# logi-cam-mt9v.net
KiCad netlist of a schematic drawn in Altium Designer
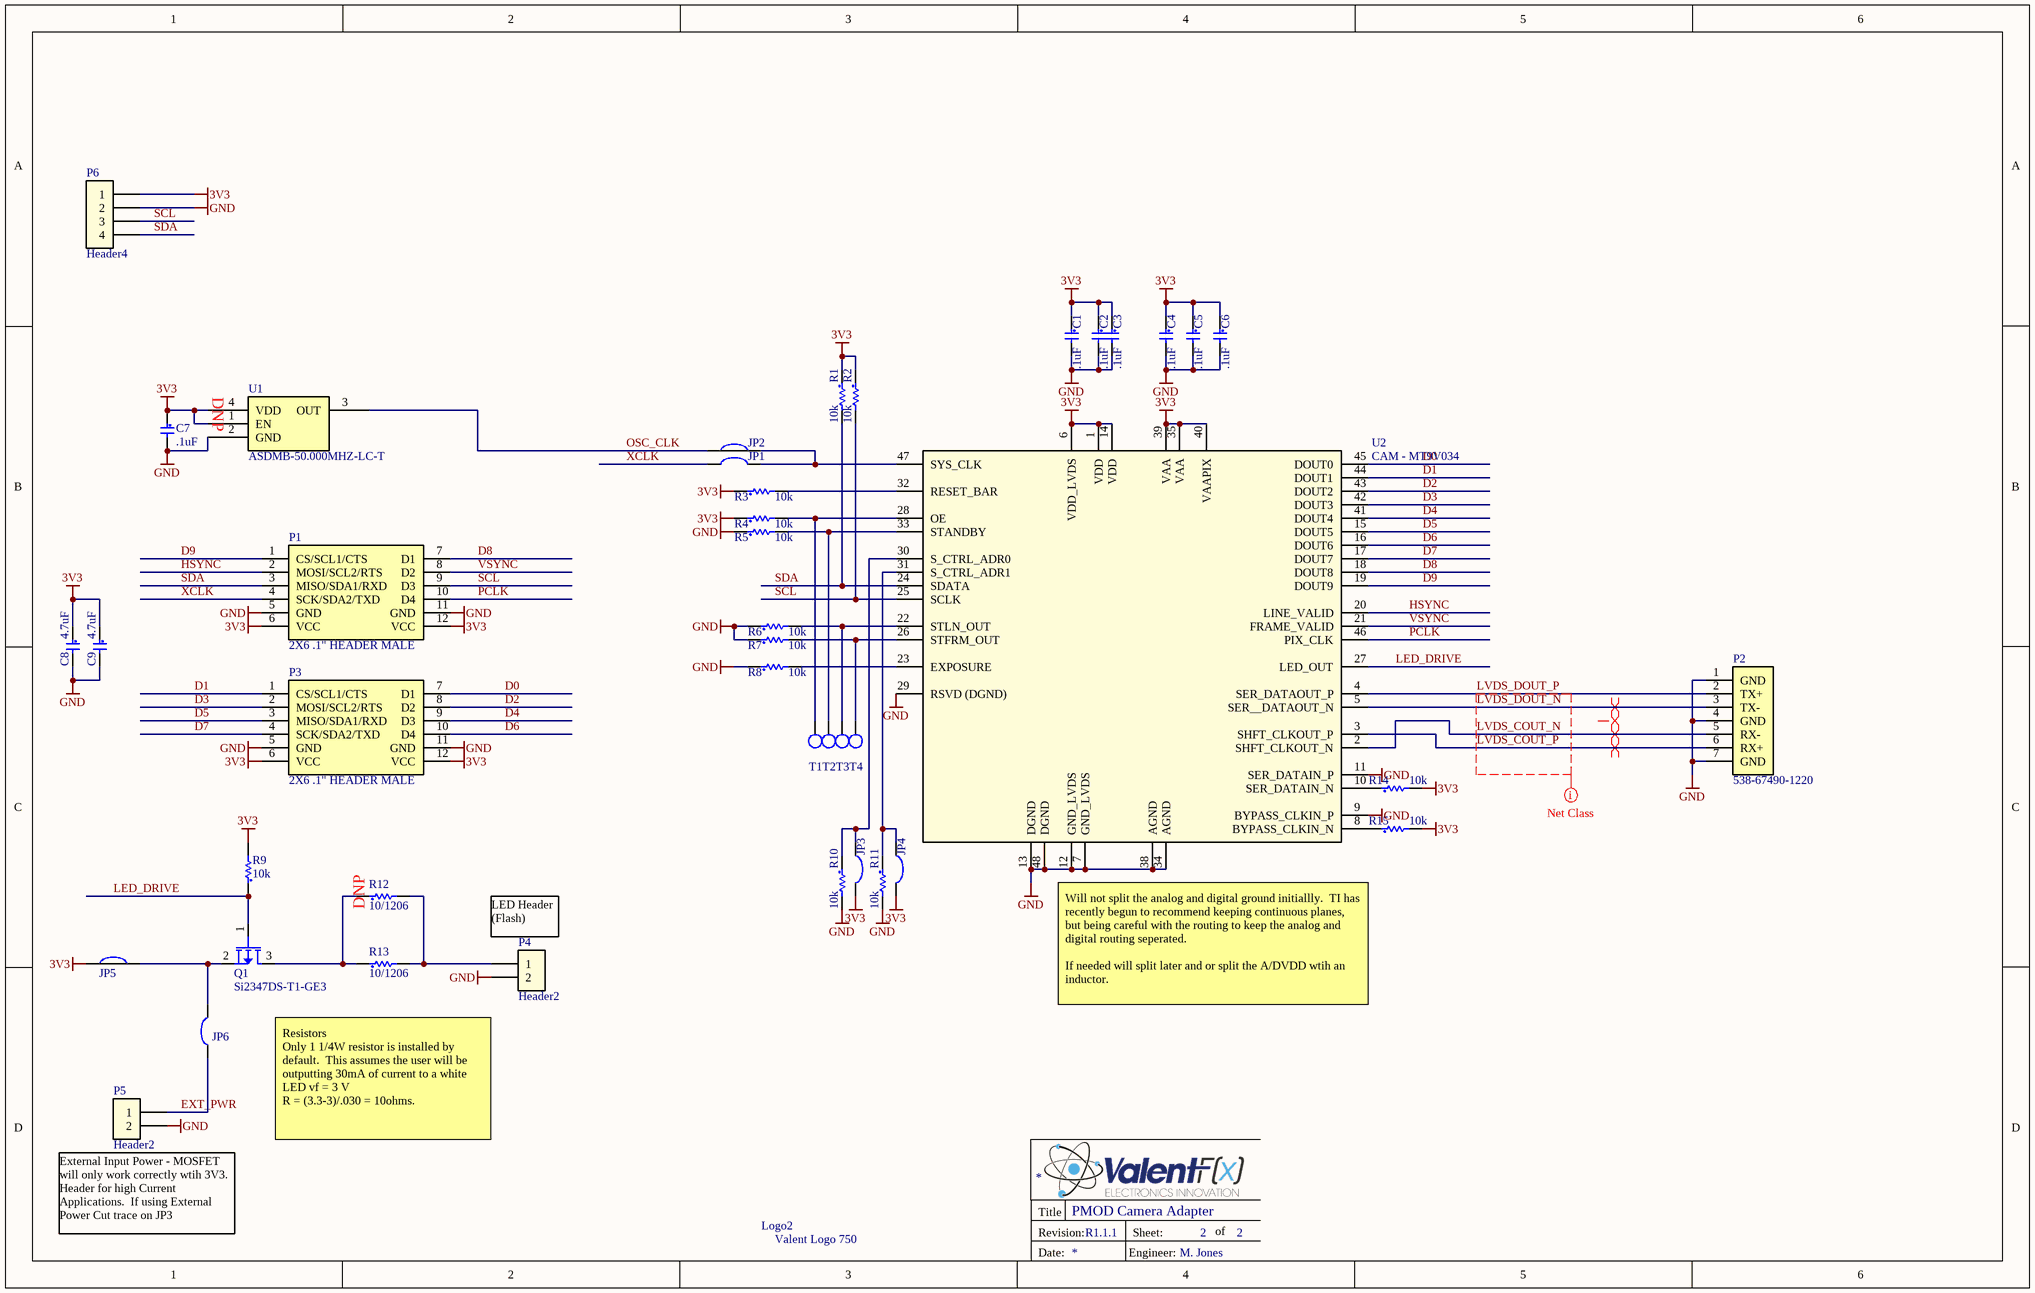
[diagram p0: logi-cam-mt9v.SchDoc]

(export (version "E")
  (design (tool "Eeschema 10.0.6"))
  (components
    (comp (ref "C1")
      (value ".1uF")
      (footprint "mRCL:C0603")
      (description ".10uF X7R 20% (MLCC) - SMD/SMT 0603 25volts")
      (fields (field (name "MANUFACTURER") "TDK") (field (name "MANUFACTURER PART NUMBER") "C1608X7R1E104MT"))
      (libsource (lib "mCapacitors") (part "C0603 - C1608X7R1E104MT"))
    )
    (comp (ref "C2")
      (value ".1uF")
      (footprint "mRCL:C0603")
      (description ".10uF X7R 20% (MLCC) - SMD/SMT 0603 25volts")
      (fields (field (name "MANUFACTURER") "TDK") (field (name "MANUFACTURER PART NUMBER") "C1608X7R1E104MT"))
      (libsource (lib "mCapacitors") (part "C0603 - C1608X7R1E104MT"))
    )
    (comp (ref "C3")
      (value ".1uF")
      (footprint "mRCL:C0603")
      (description ".10uF X7R 20% (MLCC) - SMD/SMT 0603 25volts")
      (fields (field (name "MANUFACTURER") "TDK") (field (name "MANUFACTURER PART NUMBER") "C1608X7R1E104MT"))
      (libsource (lib "mCapacitors") (part "C0603 - C1608X7R1E104MT"))
    )
    (comp (ref "C4")
      (value ".1uF")
      (footprint "mRCL:C0603")
      (description ".10uF X7R 20% (MLCC) - SMD/SMT 0603 25volts")
      (fields (field (name "MANUFACTURER") "TDK") (field (name "MANUFACTURER PART NUMBER") "C1608X7R1E104MT"))
      (libsource (lib "mCapacitors") (part "C0603 - C1608X7R1E104MT"))
    )
    (comp (ref "C5")
      (value ".1uF")
      (footprint "mRCL:C0603")
      (description ".10uF X7R 20% (MLCC) - SMD/SMT 0603 25volts")
      (fields (field (name "MANUFACTURER") "TDK") (field (name "MANUFACTURER PART NUMBER") "C1608X7R1E104MT"))
      (libsource (lib "mCapacitors") (part "C0603 - C1608X7R1E104MT"))
    )
    (comp (ref "C6")
      (value ".1uF")
      (footprint "mRCL:C0603")
      (description ".10uF X7R 20% (MLCC) - SMD/SMT 0603 25volts")
      (fields (field (name "MANUFACTURER") "TDK") (field (name "MANUFACTURER PART NUMBER") "C1608X7R1E104MT"))
      (libsource (lib "mCapacitors") (part "C0603 - C1608X7R1E104MT"))
    )
    (comp (ref "C7")
      (value ".1uF")
      (footprint "mRCL:C0603")
      (description ".10uF X7R 20% (MLCC) - SMD/SMT 0603 25volts")
      (fields (field (name "MANUFACTURER") "TDK") (field (name "MANUFACTURER PART NUMBER") "C1608X7R1E104MT"))
      (libsource (lib "mCapacitors") (part "C0603 - C1608X7R1E104MT"))
    )
    (comp (ref "C8")
      (value "4.7uF")
      (footprint "C0603 - Marked")
      (description "4.7uF 6.3volts X5R 10% (MLCC) - SMD/SMT 0603")
      (fields
        (field (name "MANUFACTURER") "Murata Electronics North America")
        (field (name "MANUFACTURER PART NUMBER") "GRM188R60J475KE19D")
      )
      (libsource (lib "mCapacitors") (part "C0603 - GRM188R60J475KE19D"))
    )
    (comp (ref "C9")
      (value "4.7uF")
      (footprint "C0603 - Marked")
      (description "4.7uF 6.3volts X5R 10% (MLCC) - SMD/SMT 0603")
      (fields
        (field (name "MANUFACTURER") "Murata Electronics North America")
        (field (name "MANUFACTURER PART NUMBER") "GRM188R60J475KE19D")
      )
      (libsource (lib "mCapacitors") (part "C0603 - GRM188R60J475KE19D"))
    )
    (comp (ref "JP1")
      (value "Solder Jumper")
      (footprint "SOLDER_JUMPER")
      (description "Solder/Configuration Jumper")
      (fields (field (name "MANUFACTURER") "n/a"))
      (libsource (lib "") (part "Solder Jumper_1"))
    )
    (comp (ref "JP2")
      (value "Solder Jumper-NC")
      (footprint "SOLDER_JUMPER-NC")
      (description "Solder/Configuration Jumper")
      (fields (field (name "MANUFACTURER") "n/a"))
      (libsource (lib "mConnector") (part "Solder Jumper-NC"))
    )
    (comp (ref "JP3")
      (value "Solder Jumper")
      (footprint "SOLDER_JUMPER")
      (description "Solder/Configuration Jumper")
      (fields (field (name "MANUFACTURER") "n/a"))
      (libsource (lib "mConnector") (part "Solder Jumper"))
    )
    (comp (ref "JP4")
      (value "Solder Jumper")
      (footprint "SOLDER_JUMPER")
      (description "Solder/Configuration Jumper")
      (fields (field (name "MANUFACTURER") "n/a"))
      (libsource (lib "mConnector") (part "Solder Jumper"))
    )
    (comp (ref "JP5")
      (value "Solder Jumper-NC")
      (footprint "SOLDER_JUMPER-NC")
      (description "Solder/Configuration Jumper")
      (fields (field (name "MANUFACTURER") "n/a"))
      (libsource (lib "mConnector") (part "Solder Jumper-NC"))
    )
    (comp (ref "JP6")
      (value "Solder Jumper")
      (footprint "SOLDER_JUMPER")
      (description "Solder/Configuration Jumper")
      (fields (field (name "MANUFACTURER") "n/a"))
      (libsource (lib "mConnector") (part "Solder Jumper"))
    )
    (comp (ref "Logo2")
      (value "Valent Logo 750")
      (footprint "VALENTFX_750-SolderMask-BOT")
      (libsource (lib "mLogos") (part "Valent Logo 750"))
    )
    (comp (ref "P1")
      (value "2X6 .1\" HEADER MALE")
      (footprint "PMOD HEADER - Male Vertical")
      (description "CONN HEADER .100\" DUAL STR 12 POS")
      (fields
        (field (name "MANUFACTURER") "Sullins Connector Solutions")
        (field (name "MANUFACTURER PART NUMBER") "PRPC006DAAN-RC")
      )
      (libsource (lib "mConnector") (part "P-MOD - PRPC006DAAN-RC"))
    )
    (comp (ref "P2")
      (value "SATA - 67490-1220")
      (footprint "SATA - 67490-3220")
      (description "SATA Data - 67490-1220")
      (fields
        (field (name "MANUFACTURER") "Molex")
        (field (name "MANUFACTURER PART NUMBER") "67490-1220")
        (field (name "SUPPLIER PART NUMBER 1") "538-67490-1220")
      )
      (libsource (lib "mConnector") (part "SATA - 67490-1220"))
    )
    (comp (ref "P3")
      (value "2X6 .1\" HEADER MALE")
      (footprint "PMOD HEADER - Male Vertical")
      (description "CONN HEADER .100\" DUAL STR 12 POS")
      (fields
        (field (name "MANUFACTURER") "Sullins Connector Solutions")
        (field (name "MANUFACTURER PART NUMBER") "PRPC006DAAN-RC")
      )
      (libsource (lib "mConnector") (part "P-MOD - PRPC006DAAN-RC"))
    )
    (comp (ref "P4")
      (value "Header2")
      (footprint "HEADER_2_40_100 THRU SIP")
      (description "Header 2 pin")
      (libsource (lib "mConnector") (part "Header2"))
    )
    (comp (ref "P5")
      (value "Header2")
      (footprint "HEADER_2_40_100 THRU SIP")
      (description "Header 2 pin")
      (libsource (lib "") (part "Header2_1"))
    )
    (comp (ref "P6")
      (value "Header4")
      (footprint "HEADER_4_40_100 THRU SIP - duplicate")
      (description "Header 4 pin")
      (libsource (lib "mConnector") (part "Header4"))
    )
    (comp (ref "Q1")
      (value "Si2347DS-T1-GE3")
      (footprint "sot-23")
      (description "MOSFET -30V .042Ohm@10V 5A P-Ch G-III")
      (fields
        (field (name "MANUFACTURER") "Vishay Semiconductors")
        (field (name "ACCEPT COMPATIBLE REPLACEMENT PART") "Yes")
      )
      (libsource (lib "mTransistor") (part "PMOS - Si2347DS-T1-GE3"))
    )
    (comp (ref "R1")
      (value "10k")
      (footprint "mRCL:R0603")
      (description "10k Thick Film Resistors - SMD 1/10watt 10Kohms 1%")
      (fields
        (field (name "MANUFACTURER") "Vishay Dale")
        (field (name "MANUFACTURER PART NUMBER") "CRCW060310K0FKEA")
      )
      (libsource (lib "mResistors") (part "R0603 - CRCW060310K0FKEA"))
    )
    (comp (ref "R2")
      (value "10k")
      (footprint "mRCL:R0603")
      (description "10k Thick Film Resistors - SMD 1/10watt 10Kohms 1%")
      (fields
        (field (name "MANUFACTURER") "Vishay Dale")
        (field (name "MANUFACTURER PART NUMBER") "CRCW060310K0FKEA")
      )
      (libsource (lib "mResistors") (part "R0603 - CRCW060310K0FKEA"))
    )
    (comp (ref "R3")
      (value "10k")
      (footprint "mRCL:R0603")
      (description "10k Thick Film Resistors - SMD 1/10watt 10Kohms 1%")
      (fields
        (field (name "MANUFACTURER") "Vishay Dale")
        (field (name "MANUFACTURER PART NUMBER") "CRCW060310K0FKEA")
      )
      (libsource (lib "mResistors") (part "R0603 - CRCW060310K0FKEA"))
    )
    (comp (ref "R4")
      (value "10k")
      (footprint "mRCL:R0603")
      (description "10k Thick Film Resistors - SMD 1/10watt 10Kohms 1%")
      (fields
        (field (name "MANUFACTURER") "Vishay Dale")
        (field (name "MANUFACTURER PART NUMBER") "CRCW060310K0FKEA")
      )
      (libsource (lib "mResistors") (part "R0603 - CRCW060310K0FKEA"))
    )
    (comp (ref "R5")
      (value "10k")
      (footprint "mRCL:R0603")
      (description "10k Thick Film Resistors - SMD 1/10watt 10Kohms 1%")
      (fields
        (field (name "MANUFACTURER") "Vishay Dale")
        (field (name "MANUFACTURER PART NUMBER") "CRCW060310K0FKEA")
      )
      (libsource (lib "mResistors") (part "R0603 - CRCW060310K0FKEA"))
    )
    (comp (ref "R6")
      (value "10k")
      (footprint "mRCL:R0603")
      (description "10k Thick Film Resistors - SMD 1/10watt 10Kohms 1%")
      (fields
        (field (name "MANUFACTURER") "Vishay Dale")
        (field (name "MANUFACTURER PART NUMBER") "CRCW060310K0FKEA")
      )
      (libsource (lib "mResistors") (part "R0603 - CRCW060310K0FKEA"))
    )
    (comp (ref "R7")
      (value "10k")
      (footprint "mRCL:R0603")
      (description "10k Thick Film Resistors - SMD 1/10watt 10Kohms 1%")
      (fields
        (field (name "MANUFACTURER") "Vishay Dale")
        (field (name "MANUFACTURER PART NUMBER") "CRCW060310K0FKEA")
      )
      (libsource (lib "mResistors") (part "R0603 - CRCW060310K0FKEA"))
    )
    (comp (ref "R8")
      (value "10k")
      (footprint "mRCL:R0603")
      (description "10k Thick Film Resistors - SMD 1/10watt 10Kohms 1%")
      (fields
        (field (name "MANUFACTURER") "Vishay Dale")
        (field (name "MANUFACTURER PART NUMBER") "CRCW060310K0FKEA")
      )
      (libsource (lib "mResistors") (part "R0603 - CRCW060310K0FKEA"))
    )
    (comp (ref "R9")
      (value "10k")
      (footprint "mRCL:R0603")
      (description "10k Thick Film Resistors - SMD 1/10watt 10Kohms 1%")
      (fields
        (field (name "MANUFACTURER") "Vishay Dale")
        (field (name "MANUFACTURER PART NUMBER") "CRCW060310K0FKEA")
      )
      (libsource (lib "mResistors") (part "R0603 - CRCW060310K0FKEA"))
    )
    (comp (ref "R10")
      (value "10k")
      (footprint "mRCL:R0603")
      (description "10k Thick Film Resistors - SMD 1/10watt 10Kohms 1%")
      (fields
        (field (name "MANUFACTURER") "Vishay Dale")
        (field (name "MANUFACTURER PART NUMBER") "CRCW060310K0FKEA")
      )
      (libsource (lib "mResistors") (part "R0603 - CRCW060310K0FKEA"))
    )
    (comp (ref "R11")
      (value "10k")
      (footprint "mRCL:R0603")
      (description "10k Thick Film Resistors - SMD 1/10watt 10Kohms 1%")
      (fields
        (field (name "MANUFACTURER") "Vishay Dale")
        (field (name "MANUFACTURER PART NUMBER") "CRCW060310K0FKEA")
      )
      (libsource (lib "mResistors") (part "R0603 - CRCW060310K0FKEA"))
    )
    (comp (ref "R12")
      (value "10/1206")
      (footprint "R1206")
      (description "RES 3.3K OHM 1/4W 1% 1206 SMD")
      (fields
        (field (name "MANUFACTURER") "Panasonic Electronic Components")
        (field (name "MANUFACTURER PART NUMBER") "ERJ-8ENF3301V")
      )
      (libsource (lib "mResistors") (part "R1206 - ERJ-8ENF3301V"))
    )
    (comp (ref "R13")
      (value "10/1206")
      (footprint "R1206")
      (description "RES 3.3K OHM 1/4W 1% 1206 SMD")
      (fields
        (field (name "MANUFACTURER") "Panasonic Electronic Components")
        (field (name "MANUFACTURER PART NUMBER") "ERJ-8ENF3301V")
      )
      (libsource (lib "mResistors") (part "R1206 - ERJ-8ENF3301V"))
    )
    (comp (ref "R14")
      (value "10k")
      (footprint "mRCL:R0603")
      (description "10k Thick Film Resistors - SMD 1/10watt 10Kohms 1%")
      (fields
        (field (name "MANUFACTURER") "Vishay Dale")
        (field (name "MANUFACTURER PART NUMBER") "CRCW060310K0FKEA")
      )
      (libsource (lib "mResistors") (part "R0603 - CRCW060310K0FKEA"))
    )
    (comp (ref "R15")
      (value "10k")
      (footprint "mRCL:R0603")
      (description "10k Thick Film Resistors - SMD 1/10watt 10Kohms 1%")
      (fields
        (field (name "MANUFACTURER") "Vishay Dale")
        (field (name "MANUFACTURER PART NUMBER") "CRCW060310K0FKEA")
      )
      (libsource (lib "mResistors") (part "R0603 - CRCW060310K0FKEA"))
    )
    (comp (ref "T1")
      (value "Test Point")
      (footprint "Tp 18-33")
      (description "Test Point Smaller Symbol")
      (libsource (lib "mConnector") (part "Test Point 2"))
    )
    (comp (ref "T2")
      (value "Test Point")
      (footprint "Tp 18-33")
      (description "Test Point Smaller Symbol")
      (libsource (lib "mConnector") (part "Test Point 2"))
    )
    (comp (ref "T3")
      (value "Test Point")
      (footprint "Tp 18-33")
      (description "Test Point Smaller Symbol")
      (libsource (lib "mConnector") (part "Test Point 2"))
    )
    (comp (ref "T4")
      (value "Test Point")
      (footprint "Tp 18-33")
      (description "Test Point Smaller Symbol")
      (libsource (lib "mConnector") (part "Test Point 2"))
    )
    (comp (ref "U1")
      (value "ASDMB-50.000MHZ-LC-T")
      (footprint "ASDMB - osc")
      (description "OSC MEMS 50.000 MHZ SMD")
      (fields (field (name "MANUFACTURER") "Abracon Corporation"))
      (libsource (lib "eIC") (part "ASDMB-50.000MHZ-LC-T"))
    )
    (comp (ref "U2")
      (value "CAM - MT9V034")
      (footprint "CAM - MT9V034 - easier")
      (description "SENSOR IMAGE VGA MONO 48-CLCC")
      (fields
        (field (name "MANUFACTURER") "Aptina LLC")
        (field (name "MANUFACTURER PART NUMBER") "MT9V034C12STM")
      )
      (libsource (lib "mCamera_Modules") (part "CAM - MT9V034"))
    )
  )
  (nets
    (net (code "1") (name "/D0") (class "Default")
      (node (ref "P3") (pin "7") (pinfunction "D1_7") (pintype "power_in"))
      (node (ref "U2") (pin "45") (pinfunction "DOUT0_45") (pintype "passive"))
    )
    (net (code "2") (name "/D1") (class "Default")
      (node (ref "P3") (pin "1") (pinfunction "CS/SCL1/CTS_1") (pintype "power_in"))
      (node (ref "U2") (pin "44") (pinfunction "DOUT1_44") (pintype "passive"))
    )
    (net (code "3") (name "/D2") (class "Default")
      (node (ref "P3") (pin "8") (pinfunction "D2_8") (pintype "power_in"))
      (node (ref "U2") (pin "43") (pinfunction "DOUT2_43") (pintype "passive"))
    )
    (net (code "4") (name "/D3") (class "Default")
      (node (ref "P3") (pin "2") (pinfunction "MOSI/SCL2/RTS_2") (pintype "power_in"))
      (node (ref "U2") (pin "42") (pinfunction "DOUT3_42") (pintype "passive"))
    )
    (net (code "5") (name "/D4") (class "Default")
      (node (ref "P3") (pin "9") (pinfunction "D3_9") (pintype "power_in"))
      (node (ref "U2") (pin "41") (pinfunction "DOUT4_41") (pintype "passive"))
    )
    (net (code "6") (name "/D5") (class "Default")
      (node (ref "P3") (pin "3") (pinfunction "MISO/SDA1/RXD_3") (pintype "power_in"))
      (node (ref "U2") (pin "15") (pinfunction "DOUT5_15") (pintype "passive"))
    )
    (net (code "7") (name "/D6") (class "Default")
      (node (ref "P3") (pin "10") (pinfunction "D4_10") (pintype "power_in"))
      (node (ref "U2") (pin "16") (pinfunction "DOUT6_16") (pintype "passive"))
    )
    (net (code "8") (name "/D7") (class "Default")
      (node (ref "P3") (pin "4") (pinfunction "SCK/SDA2/TXD_4") (pintype "power_in"))
      (node (ref "U2") (pin "17") (pinfunction "DOUT7_17") (pintype "passive"))
    )
    (net (code "9") (name "/D8") (class "Default")
      (node (ref "P1") (pin "7") (pinfunction "D1_7") (pintype "power_in"))
      (node (ref "U2") (pin "18") (pinfunction "DOUT8_18") (pintype "passive"))
    )
    (net (code "10") (name "/D9") (class "Default")
      (node (ref "P1") (pin "1") (pinfunction "CS/SCL1/CTS_1") (pintype "power_in"))
      (node (ref "U2") (pin "19") (pinfunction "DOUT9_19") (pintype "passive"))
    )
    (net (code "11") (name "/EXT_PWR") (class "Default")
      (node (ref "JP6") (pin "1") (pinfunction "1_1") (pintype "passive"))
      (node (ref "P5") (pin "1") (pinfunction "1_1") (pintype "passive"))
    )
    (net (code "12") (name "/HSYNC") (class "Default")
      (node (ref "P1") (pin "2") (pinfunction "MOSI/SCL2/RTS_2") (pintype "power_in"))
      (node (ref "U2") (pin "20") (pinfunction "LINE_VALID_20") (pintype "passive"))
    )
    (net (code "13") (name "/LED_DRIVE") (class "Default")
      (node (ref "Q1") (pin "1") (pinfunction "G_1") (pintype "passive"))
      (node (ref "R9") (pin "1") (pinfunction "1_1") (pintype "passive"))
      (node (ref "U2") (pin "27") (pinfunction "LED_OUT_27") (pintype "passive"))
    )
    (net (code "14") (name "/LVDS_COUT_N") (class "Default")
      (node (ref "P2") (pin "5") (pinfunction "RX-_5") (pintype "passive"))
      (node (ref "U2") (pin "2") (pinfunction "SHFT_CLKOUT_N_2") (pintype "passive"))
    )
    (net (code "15") (name "/LVDS_COUT_P") (class "Default")
      (node (ref "P2") (pin "6") (pinfunction "RX+_6") (pintype "passive"))
      (node (ref "U2") (pin "3") (pinfunction "SHFT_CLKOUT_P_3") (pintype "passive"))
    )
    (net (code "16") (name "/LVDS_DOUT_N") (class "Default")
      (node (ref "P2") (pin "3") (pinfunction "TX-_3") (pintype "passive"))
      (node (ref "U2") (pin "5") (pinfunction "SER__DATAOUT_N_5") (pintype "passive"))
    )
    (net (code "17") (name "/LVDS_DOUT_P") (class "Default")
      (node (ref "P2") (pin "2") (pinfunction "TX+_2") (pintype "passive"))
      (node (ref "U2") (pin "4") (pinfunction "SER_DATAOUT_P_4") (pintype "passive"))
    )
    (net (code "18") (name "/OSC_CLK") (class "Default")
      (node (ref "JP2") (pin "1") (pinfunction "1_1") (pintype "passive"))
      (node (ref "U1") (pin "3") (pinfunction "OUT_3") (pintype "passive"))
    )
    (net (code "19") (name "/PCLK") (class "Default")
      (node (ref "P1") (pin "10") (pinfunction "D4_10") (pintype "power_in"))
      (node (ref "U2") (pin "46") (pinfunction "PIX_CLK_46") (pintype "passive"))
    )
    (net (code "20") (name "/SCL") (class "Default")
      (node (ref "P1") (pin "9") (pinfunction "D3_9") (pintype "power_in"))
      (node (ref "P6") (pin "3") (pinfunction "3_3") (pintype "passive"))
      (node (ref "R2") (pin "2") (pinfunction "2_2") (pintype "passive"))
      (node (ref "U2") (pin "25") (pinfunction "SCLK_25") (pintype "passive"))
    )
    (net (code "21") (name "/SDA") (class "Default")
      (node (ref "P1") (pin "3") (pinfunction "MISO/SDA1/RXD_3") (pintype "power_in"))
      (node (ref "P6") (pin "4") (pinfunction "4_4") (pintype "passive"))
      (node (ref "R1") (pin "2") (pinfunction "2_2") (pintype "passive"))
      (node (ref "U2") (pin "24") (pinfunction "SDATA_24") (pintype "passive"))
    )
    (net (code "22") (name "/VSYNC") (class "Default")
      (node (ref "P1") (pin "8") (pinfunction "D2_8") (pintype "power_in"))
      (node (ref "U2") (pin "21") (pinfunction "FRAME_VALID_21") (pintype "passive"))
    )
    (net (code "23") (name "/XCLK") (class "Default")
      (node (ref "JP1") (pin "1") (pinfunction "1_1") (pintype "passive"))
      (node (ref "P1") (pin "4") (pinfunction "SCK/SDA2/TXD_4") (pintype "power_in"))
    )
    (net (code "24") (name "3V3") (class "Default")
      (node (ref "C1") (pin "1") (pinfunction "1_1") (pintype "passive"))
      (node (ref "C2") (pin "1") (pinfunction "1_1") (pintype "passive"))
      (node (ref "C3") (pin "1") (pinfunction "1_1") (pintype "passive"))
      (node (ref "C4") (pin "1") (pinfunction "1_1") (pintype "passive"))
      (node (ref "C5") (pin "1") (pinfunction "1_1") (pintype "passive"))
      (node (ref "C6") (pin "1") (pinfunction "1_1") (pintype "passive"))
      (node (ref "C7") (pin "1") (pinfunction "1_1") (pintype "passive"))
      (node (ref "C8") (pin "1") (pinfunction "1_1") (pintype "passive"))
      (node (ref "C9") (pin "1") (pinfunction "1_1") (pintype "passive"))
      (node (ref "JP3") (pin "2") (pinfunction "2_2") (pintype "passive"))
      (node (ref "JP4") (pin "2") (pinfunction "2_2") (pintype "passive"))
      (node (ref "JP5") (pin "1") (pinfunction "1_1") (pintype "passive"))
      (node (ref "P1") (pin "12") (pinfunction "VCC_12") (pintype "power_in"))
      (node (ref "P1") (pin "6") (pinfunction "VCC_6") (pintype "power_in"))
      (node (ref "P3") (pin "12") (pinfunction "VCC_12") (pintype "power_in"))
      (node (ref "P3") (pin "6") (pinfunction "VCC_6") (pintype "power_in"))
      (node (ref "P6") (pin "1") (pinfunction "1_1") (pintype "passive"))
      (node (ref "R1") (pin "1") (pinfunction "1_1") (pintype "passive"))
      (node (ref "R14") (pin "2") (pinfunction "2_2") (pintype "passive"))
      (node (ref "R15") (pin "2") (pinfunction "2_2") (pintype "passive"))
      (node (ref "R2") (pin "1") (pinfunction "1_1") (pintype "passive"))
      (node (ref "R3") (pin "1") (pinfunction "1_1") (pintype "passive"))
      (node (ref "R4") (pin "1") (pinfunction "1_1") (pintype "passive"))
      (node (ref "R9") (pin "2") (pinfunction "2_2") (pintype "passive"))
      (node (ref "U1") (pin "1") (pinfunction "EN_1") (pintype "passive"))
      (node (ref "U1") (pin "4") (pinfunction "VDD_4") (pintype "passive"))
      (node (ref "U2") (pin "1") (pinfunction "VDD_1") (pintype "passive"))
      (node (ref "U2") (pin "14") (pinfunction "VDD_14") (pintype "passive"))
      (node (ref "U2") (pin "35") (pinfunction "VAA_35") (pintype "passive"))
      (node (ref "U2") (pin "39") (pinfunction "VAA_39") (pintype "passive"))
      (node (ref "U2") (pin "40") (pinfunction "VAAPIX_40") (pintype "passive"))
      (node (ref "U2") (pin "6") (pinfunction "VDD_LVDS_6") (pintype "passive"))
    )
    (net (code "25") (name "GND") (class "Default")
      (node (ref "C1") (pin "2") (pinfunction "2_2") (pintype "passive"))
      (node (ref "C2") (pin "2") (pinfunction "2_2") (pintype "passive"))
      (node (ref "C3") (pin "2") (pinfunction "2_2") (pintype "passive"))
      (node (ref "C4") (pin "2") (pinfunction "2_2") (pintype "passive"))
      (node (ref "C5") (pin "2") (pinfunction "2_2") (pintype "passive"))
      (node (ref "C6") (pin "2") (pinfunction "2_2") (pintype "passive"))
      (node (ref "C7") (pin "2") (pinfunction "2_2") (pintype "passive"))
      (node (ref "C8") (pin "2") (pinfunction "2_2") (pintype "passive"))
      (node (ref "C9") (pin "2") (pinfunction "2_2") (pintype "passive"))
      (node (ref "P1") (pin "11") (pinfunction "GND_11") (pintype "power_in"))
      (node (ref "P1") (pin "5") (pinfunction "GND_5") (pintype "power_in"))
      (node (ref "P2") (pin "1") (pinfunction "GND_1") (pintype "passive"))
      (node (ref "P2") (pin "4") (pinfunction "GND_4") (pintype "passive"))
      (node (ref "P2") (pin "7") (pinfunction "GND_7") (pintype "passive"))
      (node (ref "P3") (pin "11") (pinfunction "GND_11") (pintype "power_in"))
      (node (ref "P3") (pin "5") (pinfunction "GND_5") (pintype "power_in"))
      (node (ref "P4") (pin "2") (pinfunction "2_2") (pintype "passive"))
      (node (ref "P5") (pin "2") (pinfunction "2_2") (pintype "passive"))
      (node (ref "P6") (pin "2") (pinfunction "2_2") (pintype "passive"))
      (node (ref "R10") (pin "2") (pinfunction "2_2") (pintype "passive"))
      (node (ref "R11") (pin "2") (pinfunction "2_2") (pintype "passive"))
      (node (ref "R5") (pin "1") (pinfunction "1_1") (pintype "passive"))
      (node (ref "R6") (pin "1") (pinfunction "1_1") (pintype "passive"))
      (node (ref "R7") (pin "1") (pinfunction "1_1") (pintype "passive"))
      (node (ref "R8") (pin "1") (pinfunction "1_1") (pintype "passive"))
      (node (ref "U1") (pin "2") (pinfunction "GND_2") (pintype "passive"))
      (node (ref "U2") (pin "11") (pinfunction "SER_DATAIN_P_11") (pintype "passive"))
      (node (ref "U2") (pin "12") (pinfunction "GND_LVDS_12") (pintype "passive"))
      (node (ref "U2") (pin "13") (pinfunction "DGND_13") (pintype "passive"))
      (node (ref "U2") (pin "29") (pinfunction "RSVD_(DGND)_29") (pintype "passive"))
      (node (ref "U2") (pin "34") (pinfunction "AGND_34") (pintype "passive"))
      (node (ref "U2") (pin "38") (pinfunction "AGND_38") (pintype "passive"))
      (node (ref "U2") (pin "48") (pinfunction "DGND_48") (pintype "passive"))
      (node (ref "U2") (pin "7") (pinfunction "GND_LVDS_7") (pintype "passive"))
      (node (ref "U2") (pin "9") (pinfunction "BYPASS_CLKIN_P_9") (pintype "passive"))
    )
    (net (code "26") (name "Net-(P4-Pad1)") (class "Default")
      (node (ref "P4") (pin "1") (pinfunction "1_1") (pintype "passive"))
      (node (ref "R12") (pin "2") (pinfunction "2_2") (pintype "passive"))
      (node (ref "R13") (pin "2") (pinfunction "2_2") (pintype "passive"))
    )
    (net (code "27") (name "Net-(Q1-D)") (class "Default")
      (node (ref "Q1") (pin "3") (pinfunction "D_3") (pintype "passive"))
      (node (ref "R12") (pin "1") (pinfunction "1_1") (pintype "passive"))
      (node (ref "R13") (pin "1") (pinfunction "1_1") (pintype "passive"))
    )
    (net (code "28") (name "Net-(Q1-S)") (class "Default")
      (node (ref "JP5") (pin "2") (pinfunction "2_2") (pintype "passive"))
      (node (ref "JP6") (pin "2") (pinfunction "2_2") (pintype "passive"))
      (node (ref "Q1") (pin "2") (pinfunction "S_2") (pintype "passive"))
    )
    (net (code "29") (name "Net-(U2-BYPASS_CLKIN_N)") (class "Default")
      (node (ref "R15") (pin "1") (pinfunction "1_1") (pintype "passive"))
      (node (ref "U2") (pin "8") (pinfunction "BYPASS_CLKIN_N_8") (pintype "passive"))
    )
    (net (code "30") (name "Net-(U2-EXPOSURE)") (class "Default")
      (node (ref "R8") (pin "2") (pinfunction "2_2") (pintype "passive"))
      (node (ref "U2") (pin "23") (pinfunction "EXPOSURE_23") (pintype "passive"))
    )
    (net (code "31") (name "Net-(U2-OE)") (class "Default")
      (node (ref "R4") (pin "2") (pinfunction "2_2") (pintype "passive"))
      (node (ref "T1") (pin "1") (pinfunction "1_1") (pintype "passive"))
      (node (ref "U2") (pin "28") (pinfunction "OE_28") (pintype "passive"))
    )
    (net (code "32") (name "Net-(U2-RESET_BAR)") (class "Default")
      (node (ref "R3") (pin "2") (pinfunction "2_2") (pintype "passive"))
      (node (ref "U2") (pin "32") (pinfunction "RESET_BAR_32") (pintype "passive"))
    )
    (net (code "33") (name "Net-(U2-SER_DATAIN_N)") (class "Default")
      (node (ref "R14") (pin "1") (pinfunction "1_1") (pintype "passive"))
      (node (ref "U2") (pin "10") (pinfunction "SER_DATAIN_N_10") (pintype "passive"))
    )
    (net (code "34") (name "Net-(U2-STANDBY)") (class "Default")
      (node (ref "R5") (pin "2") (pinfunction "2_2") (pintype "passive"))
      (node (ref "T2") (pin "1") (pinfunction "1_1") (pintype "passive"))
      (node (ref "U2") (pin "33") (pinfunction "STANDBY_33") (pintype "passive"))
    )
    (net (code "35") (name "Net-(U2-STFRM_OUT)") (class "Default")
      (node (ref "R7") (pin "2") (pinfunction "2_2") (pintype "passive"))
      (node (ref "T4") (pin "1") (pinfunction "1_1") (pintype "passive"))
      (node (ref "U2") (pin "26") (pinfunction "STFRM_OUT_26") (pintype "passive"))
    )
    (net (code "36") (name "Net-(U2-STLN_OUT)") (class "Default")
      (node (ref "R6") (pin "2") (pinfunction "2_2") (pintype "passive"))
      (node (ref "T3") (pin "1") (pinfunction "1_1") (pintype "passive"))
      (node (ref "U2") (pin "22") (pinfunction "STLN_OUT_22") (pintype "passive"))
    )
    (net (code "37") (name "Net-(U2-SYS_CLK)") (class "Default")
      (node (ref "JP1") (pin "2") (pinfunction "2_2") (pintype "passive"))
      (node (ref "JP2") (pin "2") (pinfunction "2_2") (pintype "passive"))
      (node (ref "U2") (pin "47") (pinfunction "SYS_CLK_47") (pintype "passive"))
    )
    (net (code "38") (name "Net-(U2-S_CTRL_ADR0)") (class "Default")
      (node (ref "JP3") (pin "1") (pinfunction "1_1") (pintype "passive"))
      (node (ref "R10") (pin "1") (pinfunction "1_1") (pintype "passive"))
      (node (ref "U2") (pin "30") (pinfunction "S_CTRL_ADR0_30") (pintype "passive"))
    )
    (net (code "39") (name "Net-(U2-S_CTRL_ADR1)") (class "Default")
      (node (ref "JP4") (pin "1") (pinfunction "1_1") (pintype "passive"))
      (node (ref "R11") (pin "1") (pinfunction "1_1") (pintype "passive"))
      (node (ref "U2") (pin "31") (pinfunction "S_CTRL_ADR1_31") (pintype "passive"))
    )
  )
)
